# SourceFollower_SOT343_Simple.net
KiCad netlist of a schematic drawn in Altium Designer
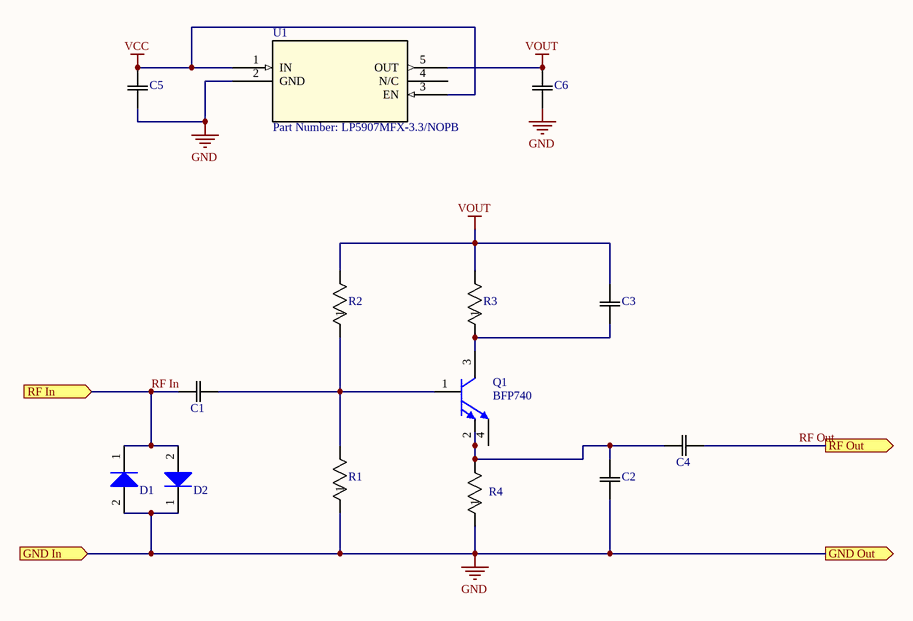
[diagram p0: SourceFollower_SOT343_Simple.SchDoc]

(export (version "E")
  (design (tool "Eeschema 10.0.6"))
  (components
    (comp (ref "C1")
      (value "Part Number: C0201C270J3GACTU")
      (footprint "C0201")
      (description "No Description Available")
      (fields
        (field (name "MANUFACTURER_PART_NUMBER") "C0201C270J3GACTU")
        (field (name "COPYRIGHT") "Copyright (C) 2018 Accelerated Designs. All rights reserved")
      )
      (libsource (lib "0201Capacitor_Yageo") (part "C0201C270J3GACTU"))
    )
    (comp (ref "C2")
      (value "Part Number: C0201C270J3GACTU")
      (footprint "C0201")
      (description "No Description Available")
      (fields
        (field (name "MANUFACTURER_PART_NUMBER") "C0201C270J3GACTU")
        (field (name "COPYRIGHT") "Copyright (C) 2018 Accelerated Designs. All rights reserved")
      )
      (libsource (lib "0201Capacitor_Yageo") (part "C0201C270J3GACTU"))
    )
    (comp (ref "C3")
      (value "Part Number: C0201C270J3GACTU")
      (footprint "C0201")
      (description "No Description Available")
      (fields
        (field (name "MANUFACTURER_PART_NUMBER") "C0201C270J3GACTU")
        (field (name "COPYRIGHT") "Copyright (C) 2018 Accelerated Designs. All rights reserved")
      )
      (libsource (lib "0201Capacitor_Yageo") (part "C0201C270J3GACTU"))
    )
    (comp (ref "C4")
      (value "Part Number: C0201C270J3GACTU")
      (footprint "C0201")
      (description "No Description Available")
      (fields
        (field (name "MANUFACTURER_PART_NUMBER") "C0201C270J3GACTU")
        (field (name "COPYRIGHT") "Copyright (C) 2018 Accelerated Designs. All rights reserved")
      )
      (libsource (lib "0201Capacitor_Yageo") (part "C0201C270J3GACTU"))
    )
    (comp (ref "C5")
      (value "Part Number: CC0402KRX7R6BB104")
      (footprint "YAG_CC0402")
      (description "No Description Available")
      (fields
        (field (name "MANUFACTURER_PART_NUMBER") "CC0402KRX7R6BB104")
        (field (name "COPYRIGHT") "Copyright (C) 2018 Accelerated Designs. All rights reserved")
      )
      (libsource (lib "0402Capacitor_Yageo") (part "CC0402KRX7R6BB10"))
    )
    (comp (ref "C6")
      (value "Part Number: CC0402KRX7R6BB104")
      (footprint "YAG_CC0402")
      (description "No Description Available")
      (fields
        (field (name "MANUFACTURER_PART_NUMBER") "CC0402KRX7R6BB104")
        (field (name "COPYRIGHT") "Copyright (C) 2018 Accelerated Designs. All rights reserved")
      )
      (libsource (lib "0402Capacitor_Yageo") (part "CC0402KRX7R6BB10"))
    )
    (comp (ref "D1")
      (value "BAT15-03W")
      (footprint "INF-SOD323_V")
      (description "Single Silicon Schottky Diode, 110 mA IF Max, SOD32, Green")
      (fields (field (name "MANUFACTURER") "Infineon"))
      (libsource (lib "Infineon_RFSchottkyDiode_SOD323") (part "BAT15-03W"))
    )
    (comp (ref "D2")
      (value "BAT15-03W")
      (footprint "INF-SOD323_V")
      (description "Single Silicon Schottky Diode, 110 mA IF Max, SOD32, Green")
      (fields (field (name "MANUFACTURER") "Infineon"))
      (libsource (lib "Infineon_RFSchottkyDiode_SOD323") (part "BAT15-03W"))
    )
    (comp (ref "Q1")
      (value "BFP740")
      (footprint "INF-SOT343_V")
      (description "NPN Silicon Germanium RF Transistor, 4 V VCEO, 45 mA IC, 27 dB Gmax, SOT343, Green")
      (fields (field (name "MANUFACTURER") "Infineon"))
      (libsource (lib "Infineon_RFBJT_SOT343") (part "BFP740"))
    )
    (comp (ref "R1")
      (value "Part Number: RC0201FR-0718KL")
      (footprint "RES_RC0201_P6XP3")
      (description "No Description Available")
      (fields
        (field (name "MANUFACTURER_PART_NUMBER") "RC0201FR-0718KL")
        (field (name "COPYRIGHT") "Copyright (C) 2018 Accelerated Designs. All rights reserved")
      )
      (libsource (lib "0201Resistor_Yageo") (part "RC0201FR-0718KL"))
    )
    (comp (ref "R2")
      (value "Part Number: RC0201FR-0718KL")
      (footprint "RES_RC0201_P6XP3")
      (description "No Description Available")
      (fields
        (field (name "MANUFACTURER_PART_NUMBER") "RC0201FR-0718KL")
        (field (name "COPYRIGHT") "Copyright (C) 2018 Accelerated Designs. All rights reserved")
      )
      (libsource (lib "0201Resistor_Yageo") (part "RC0201FR-0718KL"))
    )
    (comp (ref "R3")
      (value "Part Number: RC0201FR-0718KL")
      (footprint "RES_RC0201_P6XP3")
      (description "No Description Available")
      (fields
        (field (name "MANUFACTURER_PART_NUMBER") "RC0201FR-0718KL")
        (field (name "COPYRIGHT") "Copyright (C) 2018 Accelerated Designs. All rights reserved")
      )
      (libsource (lib "0201Resistor_Yageo") (part "RC0201FR-0718KL"))
    )
    (comp (ref "R4")
      (value "Part Number: RC0201FR-0718KL")
      (footprint "RES_RC0201_P6XP3")
      (description "No Description Available")
      (fields
        (field (name "MANUFACTURER_PART_NUMBER") "RC0201FR-0718KL")
        (field (name "COPYRIGHT") "Copyright (C) 2018 Accelerated Designs. All rights reserved")
      )
      (libsource (lib "0201Resistor_Yageo") (part "RC0201FR-0718KL"))
    )
    (comp (ref "U1")
      (value "Part Number: LP5907MFX-3.3/NOPB")
      (footprint "DBV5")
      (description "No Description Available")
      (fields
        (field (name "MANUFACTURER_PART_NUMBER") "LP5907MFX-3.3/NOPB")
        (field (name "COPYRIGHT") "Copyright (C) 2018 Accelerated Designs. All rights reserved")
      )
      (libsource (lib "TI_LDO_3V3_SOT325") (part "LP5907MFX-3.3/NO"))
    )
  )
  (nets
    (net (code "1") (name "/RF In") (class "Default")
      (node (ref "C1") (pin "1") (pinfunction "1_1") (pintype "passive"))
      (node (ref "D1") (pin "1") (pinfunction "K_1") (pintype "passive"))
      (node (ref "D2") (pin "2") (pinfunction "A_2") (pintype "passive"))
    )
    (net (code "2") (name "/RF Out") (class "Default")
      (node (ref "C4") (pin "1") (pinfunction "1_1") (pintype "passive"))
    )
    (net (code "3") (name "GND") (class "Default")
      (node (ref "C2") (pin "1") (pinfunction "1_1") (pintype "passive"))
      (node (ref "C5") (pin "1") (pinfunction "1_1") (pintype "passive"))
      (node (ref "C6") (pin "1") (pinfunction "1_1") (pintype "passive"))
      (node (ref "D1") (pin "2") (pinfunction "A_2") (pintype "passive"))
      (node (ref "D2") (pin "1") (pinfunction "K_1") (pintype "passive"))
      (node (ref "R1") (pin "1") (pinfunction "1_1") (pintype "passive"))
      (node (ref "R4") (pin "1") (pinfunction "1_1") (pintype "passive"))
      (node (ref "U1") (pin "2") (pinfunction "GND_2") (pintype "power_in"))
    )
    (net (code "4") (name "Net-(C2-Pad2)") (class "Default")
      (node (ref "C2") (pin "2") (pinfunction "2_2") (pintype "passive"))
      (node (ref "C4") (pin "2") (pinfunction "2_2") (pintype "passive"))
      (node (ref "Q1") (pin "2") (pinfunction "E_2") (pintype "passive"))
      (node (ref "R4") (pin "2") (pinfunction "2_2") (pintype "passive"))
    )
    (net (code "5") (name "Net-(Q1-B)") (class "Default")
      (node (ref "C1") (pin "2") (pinfunction "2_2") (pintype "passive"))
      (node (ref "Q1") (pin "1") (pinfunction "B_1") (pintype "passive"))
      (node (ref "R1") (pin "2") (pinfunction "2_2") (pintype "passive"))
      (node (ref "R2") (pin "1") (pinfunction "1_1") (pintype "passive"))
    )
    (net (code "6") (name "Net-(Q1-C)") (class "Default")
      (node (ref "C3") (pin "1") (pinfunction "1_1") (pintype "passive"))
      (node (ref "Q1") (pin "3") (pinfunction "C_3") (pintype "passive"))
      (node (ref "R3") (pin "1") (pinfunction "1_1") (pintype "passive"))
    )
    (net (code "7") (name "VCC") (class "Default")
      (node (ref "C5") (pin "2") (pinfunction "2_2") (pintype "passive"))
      (node (ref "U1") (pin "1") (pinfunction "IN_1") (pintype "input"))
      (node (ref "U1") (pin "3") (pinfunction "EN_3") (pintype "input"))
    )
    (net (code "8") (name "VOUT") (class "Default")
      (node (ref "C3") (pin "2") (pinfunction "2_2") (pintype "passive"))
      (node (ref "C6") (pin "2") (pinfunction "2_2") (pintype "passive"))
      (node (ref "R2") (pin "2") (pinfunction "2_2") (pintype "passive"))
      (node (ref "R3") (pin "2") (pinfunction "2_2") (pintype "passive"))
      (node (ref "U1") (pin "5") (pinfunction "OUT_5") (pintype "output"))
    )
    (net (code "9") (name "unconnected-(Q1-E-Pad4)") (class "Default")
      (node (ref "Q1") (pin "4") (pinfunction "E_4") (pintype "passive"))
    )
    (net (code "10") (name "unconnected-(U1-N{slash}C-Pad4)") (class "Default")
      (node (ref "U1") (pin "4") (pinfunction "N/C_4") (pintype "passive"))
    )
  )
)
